# Connect.net
KiCad netlist of a schematic drawn in Altium Designer
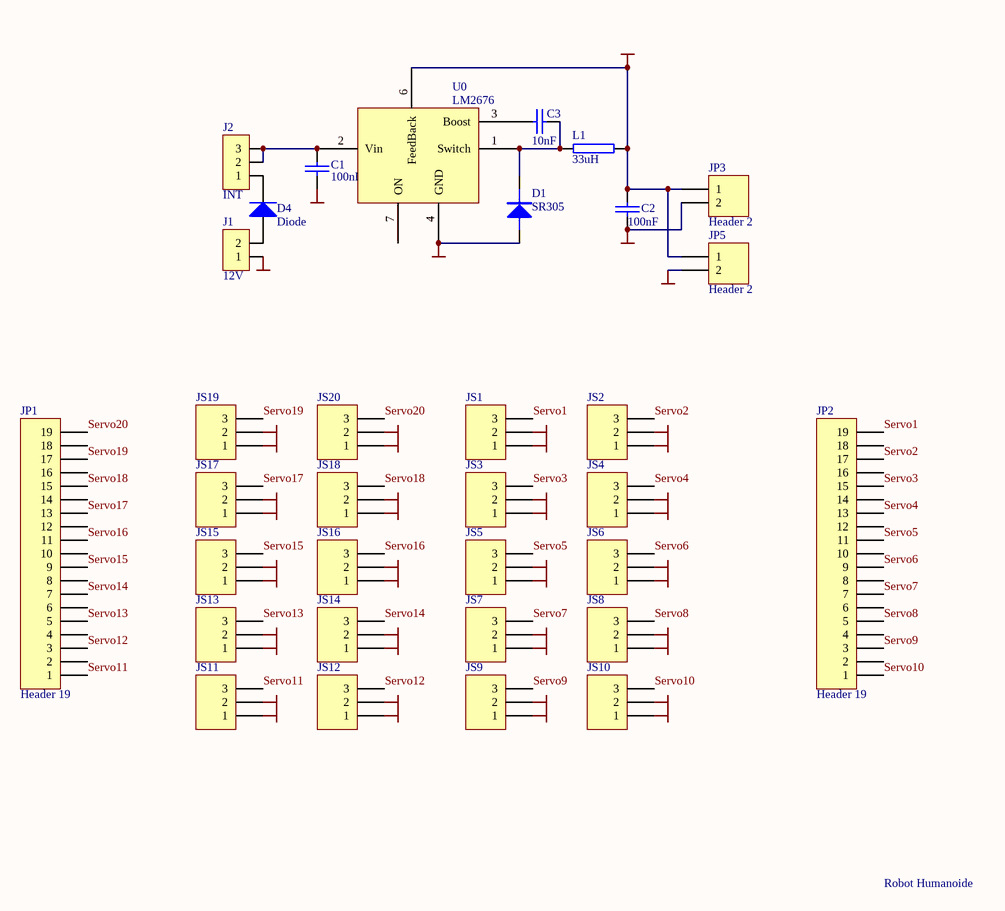
[diagram p0: Connect.SCHDOC]

(export (version "E")
  (design (tool "Eeschema 10.0.6"))
  (components
    (comp (ref "C1") (value "100nF") (footprint "0805") (libsource (lib "*") (part "CAP")))
    (comp (ref "C2") (value "100nF") (footprint "0805") (libsource (lib "*") (part "CAP")))
    (comp (ref "C3") (value "10nF") (footprint "0805") (libsource (lib "*") (part "CONDO")))
    (comp (ref "D1") (value "SR305") (footprint "1812") (libsource (lib "*") (part "DIODE")))
    (comp (ref "D4")
      (value "Diode")
      (footprint "DSO-C2/X3.3")
      (description "Default Diode")
      (fields (field (name "PUBLISHER") "Altium Limited"))
      (libsource (lib "Miscellaneous Devices") (part "Diode"))
    )
    (comp (ref "J1") (value "12V") (footprint "CON2") (libsource (lib "*") (part "CON2")))
    (comp (ref "J2") (value "INT") (footprint "TSIP3") (libsource (lib "*") (part "TCON3")))
    (comp (ref "JP1")
      (value "Header 19")
      (footprint "HDR1X19")
      (description "Header, 19-Pin")
      (fields (field (name "PUBLISHER") "Altium Limited"))
      (libsource (lib "Miscellaneous Connectors") (part "Header 19"))
    )
    (comp (ref "JP2")
      (value "Header 19")
      (footprint "HDR1X19")
      (description "Header, 19-Pin")
      (fields (field (name "PUBLISHER") "Altium Limited"))
      (libsource (lib "Miscellaneous Connectors") (part "Header 19"))
    )
    (comp (ref "JP3")
      (value "Header 2")
      (footprint "HDR1X2")
      (description "Header, 2-Pin")
      (fields (field (name "PUBLISHER") "Altium Limited"))
      (libsource (lib "Miscellaneous Connectors") (part "Header 2"))
    )
    (comp (ref "JP5")
      (value "Header 2")
      (footprint "HDR1X2")
      (description "Header, 2-Pin")
      (fields (field (name "PUBLISHER") "Altium Limited"))
      (libsource (lib "Miscellaneous Connectors") (part "Header 2"))
    )
    (comp (ref "JS1")
      (value "Header 3")
      (footprint "HDR1X3")
      (description "Header, 3-Pin")
      (fields (field (name "PUBLISHER") "Altium Limited"))
      (libsource (lib "Miscellaneous Connectors") (part "Header 3"))
    )
    (comp (ref "JS2")
      (value "Header 3")
      (footprint "HDR1X3")
      (description "Header, 3-Pin")
      (fields (field (name "PUBLISHER") "Altium Limited"))
      (libsource (lib "Miscellaneous Connectors") (part "Header 3"))
    )
    (comp (ref "JS3")
      (value "Header 3")
      (footprint "HDR1X3")
      (description "Header, 3-Pin")
      (fields (field (name "PUBLISHER") "Altium Limited"))
      (libsource (lib "Miscellaneous Connectors") (part "Header 3"))
    )
    (comp (ref "JS4")
      (value "Header 3")
      (footprint "HDR1X3")
      (description "Header, 3-Pin")
      (fields (field (name "PUBLISHER") "Altium Limited"))
      (libsource (lib "Miscellaneous Connectors") (part "Header 3"))
    )
    (comp (ref "JS5")
      (value "Header 3")
      (footprint "HDR1X3")
      (description "Header, 3-Pin")
      (fields (field (name "PUBLISHER") "Altium Limited"))
      (libsource (lib "Miscellaneous Connectors") (part "Header 3"))
    )
    (comp (ref "JS6")
      (value "Header 3")
      (footprint "HDR1X3")
      (description "Header, 3-Pin")
      (fields (field (name "PUBLISHER") "Altium Limited"))
      (libsource (lib "Miscellaneous Connectors") (part "Header 3"))
    )
    (comp (ref "JS7")
      (value "Header 3")
      (footprint "HDR1X3")
      (description "Header, 3-Pin")
      (fields (field (name "PUBLISHER") "Altium Limited"))
      (libsource (lib "Miscellaneous Connectors") (part "Header 3"))
    )
    (comp (ref "JS8")
      (value "Header 3")
      (footprint "HDR1X3")
      (description "Header, 3-Pin")
      (fields (field (name "PUBLISHER") "Altium Limited"))
      (libsource (lib "Miscellaneous Connectors") (part "Header 3"))
    )
    (comp (ref "JS9")
      (value "Header 3")
      (footprint "HDR1X3")
      (description "Header, 3-Pin")
      (fields (field (name "PUBLISHER") "Altium Limited"))
      (libsource (lib "Miscellaneous Connectors") (part "Header 3"))
    )
    (comp (ref "JS10")
      (value "Header 3")
      (footprint "HDR1X3")
      (description "Header, 3-Pin")
      (fields (field (name "PUBLISHER") "Altium Limited"))
      (libsource (lib "Miscellaneous Connectors") (part "Header 3"))
    )
    (comp (ref "JS11")
      (value "Header 3")
      (footprint "HDR1X3")
      (description "Header, 3-Pin")
      (fields (field (name "PUBLISHER") "Altium Limited"))
      (libsource (lib "Miscellaneous Connectors") (part "Header 3"))
    )
    (comp (ref "JS12")
      (value "Header 3")
      (footprint "HDR1X3")
      (description "Header, 3-Pin")
      (fields (field (name "PUBLISHER") "Altium Limited"))
      (libsource (lib "Miscellaneous Connectors") (part "Header 3"))
    )
    (comp (ref "JS13")
      (value "Header 3")
      (footprint "HDR1X3")
      (description "Header, 3-Pin")
      (fields (field (name "PUBLISHER") "Altium Limited"))
      (libsource (lib "Miscellaneous Connectors") (part "Header 3"))
    )
    (comp (ref "JS14")
      (value "Header 3")
      (footprint "HDR1X3")
      (description "Header, 3-Pin")
      (fields (field (name "PUBLISHER") "Altium Limited"))
      (libsource (lib "Miscellaneous Connectors") (part "Header 3"))
    )
    (comp (ref "JS15")
      (value "Header 3")
      (footprint "HDR1X3")
      (description "Header, 3-Pin")
      (fields (field (name "PUBLISHER") "Altium Limited"))
      (libsource (lib "Miscellaneous Connectors") (part "Header 3"))
    )
    (comp (ref "JS16")
      (value "Header 3")
      (footprint "HDR1X3")
      (description "Header, 3-Pin")
      (fields (field (name "PUBLISHER") "Altium Limited"))
      (libsource (lib "Miscellaneous Connectors") (part "Header 3"))
    )
    (comp (ref "JS17")
      (value "Header 3")
      (footprint "HDR1X3")
      (description "Header, 3-Pin")
      (fields (field (name "PUBLISHER") "Altium Limited"))
      (libsource (lib "Miscellaneous Connectors") (part "Header 3"))
    )
    (comp (ref "JS18")
      (value "Header 3")
      (footprint "HDR1X3")
      (description "Header, 3-Pin")
      (fields (field (name "PUBLISHER") "Altium Limited"))
      (libsource (lib "Miscellaneous Connectors") (part "Header 3"))
    )
    (comp (ref "JS19")
      (value "Header 3")
      (footprint "HDR1X3")
      (description "Header, 3-Pin")
      (fields (field (name "PUBLISHER") "Altium Limited"))
      (libsource (lib "Miscellaneous Connectors") (part "Header 3"))
    )
    (comp (ref "JS20")
      (value "Header 3")
      (footprint "HDR1X3")
      (description "Header, 3-Pin")
      (fields (field (name "PUBLISHER") "Altium Limited"))
      (libsource (lib "Miscellaneous Connectors") (part "Header 3"))
    )
    (comp (ref "L1")
      (value "33uH")
      (footprint "TRES")
      (fields (field (name "PUBLISHER") "*"))
      (libsource (lib "*") (part "RES2"))
    )
    (comp (ref "U0") (value "LM2676") (footprint "LM2676") (libsource (lib "*") (part "LM2676")))
  )
  (nets
    (net (code "1") (name "/Servo1") (class "Default")
      (node (ref "JP2") (pin "19") (pinfunction "19_19") (pintype "passive"))
      (node (ref "JS1") (pin "3") (pinfunction "3_3") (pintype "passive"))
    )
    (net (code "2") (name "/Servo2") (class "Default")
      (node (ref "JP2") (pin "17") (pinfunction "17_17") (pintype "passive"))
      (node (ref "JS2") (pin "3") (pinfunction "3_3") (pintype "passive"))
    )
    (net (code "3") (name "/Servo3") (class "Default")
      (node (ref "JP2") (pin "15") (pinfunction "15_15") (pintype "passive"))
      (node (ref "JS3") (pin "3") (pinfunction "3_3") (pintype "passive"))
    )
    (net (code "4") (name "/Servo4") (class "Default")
      (node (ref "JP2") (pin "13") (pinfunction "13_13") (pintype "passive"))
      (node (ref "JS4") (pin "3") (pinfunction "3_3") (pintype "passive"))
    )
    (net (code "5") (name "/Servo5") (class "Default")
      (node (ref "JP2") (pin "11") (pinfunction "11_11") (pintype "passive"))
      (node (ref "JS5") (pin "3") (pinfunction "3_3") (pintype "passive"))
    )
    (net (code "6") (name "/Servo6") (class "Default")
      (node (ref "JP2") (pin "9") (pinfunction "9_9") (pintype "passive"))
      (node (ref "JS6") (pin "3") (pinfunction "3_3") (pintype "passive"))
    )
    (net (code "7") (name "/Servo7") (class "Default")
      (node (ref "JP2") (pin "7") (pinfunction "7_7") (pintype "passive"))
      (node (ref "JS7") (pin "3") (pinfunction "3_3") (pintype "passive"))
    )
    (net (code "8") (name "/Servo8") (class "Default")
      (node (ref "JP2") (pin "5") (pinfunction "5_5") (pintype "passive"))
      (node (ref "JS8") (pin "3") (pinfunction "3_3") (pintype "passive"))
    )
    (net (code "9") (name "/Servo9") (class "Default")
      (node (ref "JP2") (pin "3") (pinfunction "3_3") (pintype "passive"))
      (node (ref "JS9") (pin "3") (pinfunction "3_3") (pintype "passive"))
    )
    (net (code "10") (name "/Servo10") (class "Default")
      (node (ref "JP2") (pin "1") (pinfunction "1_1") (pintype "passive"))
      (node (ref "JS10") (pin "3") (pinfunction "3_3") (pintype "passive"))
    )
    (net (code "11") (name "/Servo11") (class "Default")
      (node (ref "JP1") (pin "1") (pinfunction "1_1") (pintype "passive"))
      (node (ref "JS11") (pin "3") (pinfunction "3_3") (pintype "passive"))
    )
    (net (code "12") (name "/Servo12") (class "Default")
      (node (ref "JP1") (pin "3") (pinfunction "3_3") (pintype "passive"))
      (node (ref "JS12") (pin "3") (pinfunction "3_3") (pintype "passive"))
    )
    (net (code "13") (name "/Servo13") (class "Default")
      (node (ref "JP1") (pin "5") (pinfunction "5_5") (pintype "passive"))
      (node (ref "JS13") (pin "3") (pinfunction "3_3") (pintype "passive"))
    )
    (net (code "14") (name "/Servo14") (class "Default")
      (node (ref "JP1") (pin "7") (pinfunction "7_7") (pintype "passive"))
      (node (ref "JS14") (pin "3") (pinfunction "3_3") (pintype "passive"))
    )
    (net (code "15") (name "/Servo15") (class "Default")
      (node (ref "JP1") (pin "9") (pinfunction "9_9") (pintype "passive"))
      (node (ref "JS15") (pin "3") (pinfunction "3_3") (pintype "passive"))
    )
    (net (code "16") (name "/Servo16") (class "Default")
      (node (ref "JP1") (pin "11") (pinfunction "11_11") (pintype "passive"))
      (node (ref "JS16") (pin "3") (pinfunction "3_3") (pintype "passive"))
    )
    (net (code "17") (name "/Servo17") (class "Default")
      (node (ref "JP1") (pin "13") (pinfunction "13_13") (pintype "passive"))
      (node (ref "JS17") (pin "3") (pinfunction "3_3") (pintype "passive"))
    )
    (net (code "18") (name "/Servo18") (class "Default")
      (node (ref "JP1") (pin "15") (pinfunction "15_15") (pintype "passive"))
      (node (ref "JS18") (pin "3") (pinfunction "3_3") (pintype "passive"))
    )
    (net (code "19") (name "/Servo19") (class "Default")
      (node (ref "JP1") (pin "17") (pinfunction "17_17") (pintype "passive"))
      (node (ref "JS19") (pin "3") (pinfunction "3_3") (pintype "passive"))
    )
    (net (code "20") (name "/Servo20") (class "Default")
      (node (ref "JP1") (pin "19") (pinfunction "19_19") (pintype "passive"))
      (node (ref "JS20") (pin "3") (pinfunction "3_3") (pintype "passive"))
    )
    (net (code "21") (name "5V") (class "Default")
      (node (ref "C2") (pin "2") (pintype "passive"))
      (node (ref "JP3") (pin "1") (pinfunction "1_1") (pintype "passive"))
      (node (ref "JP5") (pin "1") (pinfunction "1_1") (pintype "passive"))
      (node (ref "JS1") (pin "2") (pinfunction "2_2") (pintype "passive"))
      (node (ref "JS10") (pin "2") (pinfunction "2_2") (pintype "passive"))
      (node (ref "JS11") (pin "2") (pinfunction "2_2") (pintype "passive"))
      (node (ref "JS12") (pin "2") (pinfunction "2_2") (pintype "passive"))
      (node (ref "JS13") (pin "2") (pinfunction "2_2") (pintype "passive"))
      (node (ref "JS14") (pin "2") (pinfunction "2_2") (pintype "passive"))
      (node (ref "JS15") (pin "2") (pinfunction "2_2") (pintype "passive"))
      (node (ref "JS16") (pin "2") (pinfunction "2_2") (pintype "passive"))
      (node (ref "JS17") (pin "2") (pinfunction "2_2") (pintype "passive"))
      (node (ref "JS18") (pin "2") (pinfunction "2_2") (pintype "passive"))
      (node (ref "JS19") (pin "2") (pinfunction "2_2") (pintype "passive"))
      (node (ref "JS2") (pin "2") (pinfunction "2_2") (pintype "passive"))
      (node (ref "JS20") (pin "2") (pinfunction "2_2") (pintype "passive"))
      (node (ref "JS3") (pin "2") (pinfunction "2_2") (pintype "passive"))
      (node (ref "JS4") (pin "2") (pinfunction "2_2") (pintype "passive"))
      (node (ref "JS5") (pin "2") (pinfunction "2_2") (pintype "passive"))
      (node (ref "JS6") (pin "2") (pinfunction "2_2") (pintype "passive"))
      (node (ref "JS7") (pin "2") (pinfunction "2_2") (pintype "passive"))
      (node (ref "JS8") (pin "2") (pinfunction "2_2") (pintype "passive"))
      (node (ref "JS9") (pin "2") (pinfunction "2_2") (pintype "passive"))
      (node (ref "L1") (pin "2") (pintype "passive"))
      (node (ref "U0") (pin "6") (pinfunction "FeedBack_6") (pintype "passive"))
    )
    (net (code "22") (name "GND") (class "Default")
      (node (ref "C1") (pin "1") (pintype "passive"))
      (node (ref "C2") (pin "1") (pintype "passive"))
      (node (ref "D1") (pin "2") (pintype "passive"))
      (node (ref "J1") (pin "1") (pinfunction "1_1") (pintype "passive"))
      (node (ref "JP3") (pin "2") (pinfunction "2_2") (pintype "passive"))
      (node (ref "JP5") (pin "2") (pinfunction "2_2") (pintype "passive"))
      (node (ref "JS1") (pin "1") (pinfunction "1_1") (pintype "passive"))
      (node (ref "JS10") (pin "1") (pinfunction "1_1") (pintype "passive"))
      (node (ref "JS11") (pin "1") (pinfunction "1_1") (pintype "passive"))
      (node (ref "JS12") (pin "1") (pinfunction "1_1") (pintype "passive"))
      (node (ref "JS13") (pin "1") (pinfunction "1_1") (pintype "passive"))
      (node (ref "JS14") (pin "1") (pinfunction "1_1") (pintype "passive"))
      (node (ref "JS15") (pin "1") (pinfunction "1_1") (pintype "passive"))
      (node (ref "JS16") (pin "1") (pinfunction "1_1") (pintype "passive"))
      (node (ref "JS17") (pin "1") (pinfunction "1_1") (pintype "passive"))
      (node (ref "JS18") (pin "1") (pinfunction "1_1") (pintype "passive"))
      (node (ref "JS19") (pin "1") (pinfunction "1_1") (pintype "passive"))
      (node (ref "JS2") (pin "1") (pinfunction "1_1") (pintype "passive"))
      (node (ref "JS20") (pin "1") (pinfunction "1_1") (pintype "passive"))
      (node (ref "JS3") (pin "1") (pinfunction "1_1") (pintype "passive"))
      (node (ref "JS4") (pin "1") (pinfunction "1_1") (pintype "passive"))
      (node (ref "JS5") (pin "1") (pinfunction "1_1") (pintype "passive"))
      (node (ref "JS6") (pin "1") (pinfunction "1_1") (pintype "passive"))
      (node (ref "JS7") (pin "1") (pinfunction "1_1") (pintype "passive"))
      (node (ref "JS8") (pin "1") (pinfunction "1_1") (pintype "passive"))
      (node (ref "JS9") (pin "1") (pinfunction "1_1") (pintype "passive"))
      (node (ref "U0") (pin "4") (pinfunction "GND_4") (pintype "passive"))
    )
    (net (code "23") (name "Net-(D4-A)") (class "Default")
      (node (ref "D4") (pin "1") (pinfunction "A_1") (pintype "passive"))
      (node (ref "J1") (pin "2") (pinfunction "2_2") (pintype "passive"))
    )
    (net (code "24") (name "Net-(D4-K)") (class "Default")
      (node (ref "D4") (pin "2") (pinfunction "K_2") (pintype "passive"))
      (node (ref "J2") (pin "1") (pinfunction "1_1") (pintype "passive"))
    )
    (net (code "25") (name "Net-(U0-Boost)") (class "Default")
      (node (ref "C3") (pin "1") (pintype "passive"))
      (node (ref "U0") (pin "3") (pinfunction "Boost_3") (pintype "passive"))
    )
    (net (code "26") (name "Net-(U0-Switch)") (class "Default")
      (node (ref "C3") (pin "2") (pintype "passive"))
      (node (ref "D1") (pin "1") (pintype "passive"))
      (node (ref "L1") (pin "1") (pintype "passive"))
      (node (ref "U0") (pin "1") (pinfunction "Switch_1") (pintype "passive"))
    )
    (net (code "27") (name "Net-(U0-Vin)") (class "Default")
      (node (ref "C1") (pin "2") (pintype "passive"))
      (node (ref "J2") (pin "2") (pinfunction "2_2") (pintype "passive"))
      (node (ref "J2") (pin "3") (pinfunction "3_3") (pintype "passive"))
      (node (ref "U0") (pin "2") (pinfunction "Vin_2") (pintype "passive"))
    )
    (net (code "28") (name "unconnected-(JP1-Pad2)") (class "Default")
      (node (ref "JP1") (pin "2") (pinfunction "2_2") (pintype "passive"))
    )
    (net (code "29") (name "unconnected-(JP1-Pad4)") (class "Default")
      (node (ref "JP1") (pin "4") (pinfunction "4_4") (pintype "passive"))
    )
    (net (code "30") (name "unconnected-(JP1-Pad6)") (class "Default")
      (node (ref "JP1") (pin "6") (pinfunction "6_6") (pintype "passive"))
    )
    (net (code "31") (name "unconnected-(JP1-Pad8)") (class "Default")
      (node (ref "JP1") (pin "8") (pinfunction "8_8") (pintype "passive"))
    )
    (net (code "32") (name "unconnected-(JP1-Pad10)") (class "Default")
      (node (ref "JP1") (pin "10") (pinfunction "10_10") (pintype "passive"))
    )
    (net (code "33") (name "unconnected-(JP1-Pad12)") (class "Default")
      (node (ref "JP1") (pin "12") (pinfunction "12_12") (pintype "passive"))
    )
    (net (code "34") (name "unconnected-(JP1-Pad14)") (class "Default")
      (node (ref "JP1") (pin "14") (pinfunction "14_14") (pintype "passive"))
    )
    (net (code "35") (name "unconnected-(JP1-Pad16)") (class "Default")
      (node (ref "JP1") (pin "16") (pinfunction "16_16") (pintype "passive"))
    )
    (net (code "36") (name "unconnected-(JP1-Pad18)") (class "Default")
      (node (ref "JP1") (pin "18") (pinfunction "18_18") (pintype "passive"))
    )
    (net (code "37") (name "unconnected-(JP2-Pad2)") (class "Default")
      (node (ref "JP2") (pin "2") (pinfunction "2_2") (pintype "passive"))
    )
    (net (code "38") (name "unconnected-(JP2-Pad4)") (class "Default")
      (node (ref "JP2") (pin "4") (pinfunction "4_4") (pintype "passive"))
    )
    (net (code "39") (name "unconnected-(JP2-Pad6)") (class "Default")
      (node (ref "JP2") (pin "6") (pinfunction "6_6") (pintype "passive"))
    )
    (net (code "40") (name "unconnected-(JP2-Pad8)") (class "Default")
      (node (ref "JP2") (pin "8") (pinfunction "8_8") (pintype "passive"))
    )
    (net (code "41") (name "unconnected-(JP2-Pad10)") (class "Default")
      (node (ref "JP2") (pin "10") (pinfunction "10_10") (pintype "passive"))
    )
    (net (code "42") (name "unconnected-(JP2-Pad12)") (class "Default")
      (node (ref "JP2") (pin "12") (pinfunction "12_12") (pintype "passive"))
    )
    (net (code "43") (name "unconnected-(JP2-Pad14)") (class "Default")
      (node (ref "JP2") (pin "14") (pinfunction "14_14") (pintype "passive"))
    )
    (net (code "44") (name "unconnected-(JP2-Pad16)") (class "Default")
      (node (ref "JP2") (pin "16") (pinfunction "16_16") (pintype "passive"))
    )
    (net (code "45") (name "unconnected-(JP2-Pad18)") (class "Default")
      (node (ref "JP2") (pin "18") (pinfunction "18_18") (pintype "passive"))
    )
    (net (code "46") (name "unconnected-(U0-ON-Pad7)") (class "Default")
      (node (ref "U0") (pin "7") (pinfunction "ON_7") (pintype "passive"))
    )
  )
)
